# IMU_Section.net
KiCad netlist of a schematic drawn in Altium Designer
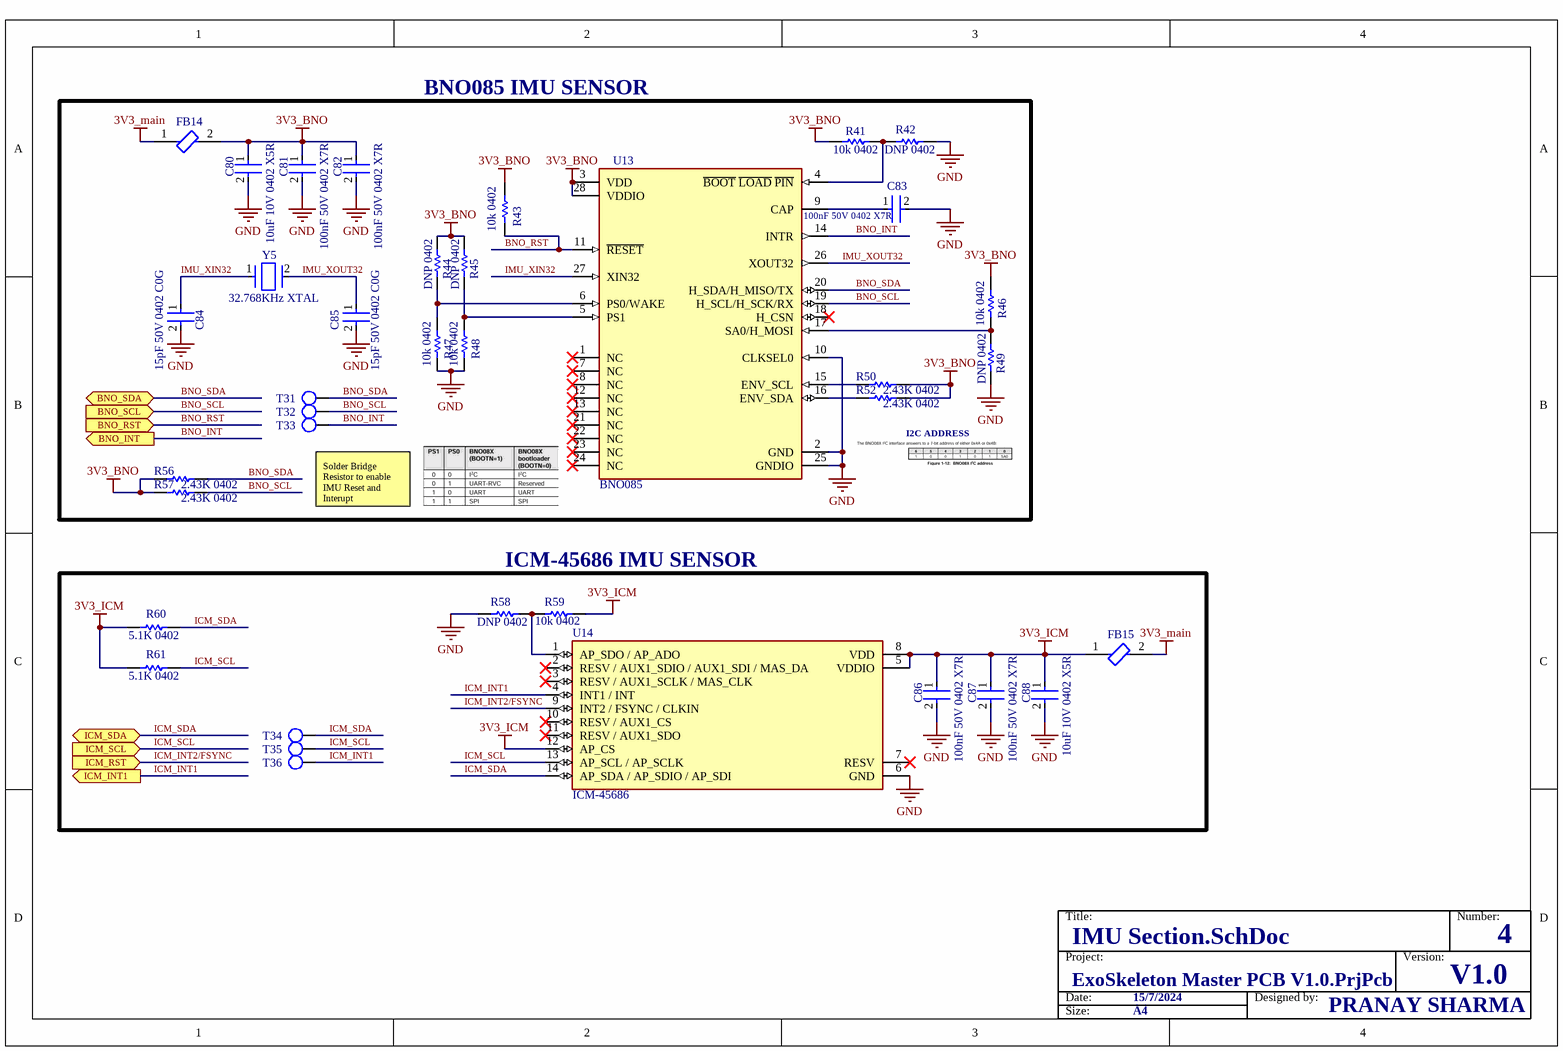
[diagram p0: IMU Section.SchDoc]

(export (version "E")
  (design (tool "Eeschema 10.0.6"))
  (components
    (comp (ref "C80")
      (value "10uF 10V 0402 X5R")
      (footprint "Res, Cap, Ind, LED, FB_Lib:0402 IPC CLASS C CAPACITOR")
      (libsource (lib "Capacitor_Lib") (part "10uF 10V 0402 X5R"))
    )
    (comp (ref "C81")
      (value "100nF 50V 0402 X7R")
      (footprint "Res, Cap, Ind, LED, FB_Lib:0402 IPC CLASS C CAPACITOR")
      (libsource (lib "Capacitor_Lib") (part "100nF 50V 0402 X7R"))
    )
    (comp (ref "C82")
      (value "100nF 50V 0402 X7R")
      (footprint "Res, Cap, Ind, LED, FB_Lib:0402 IPC CLASS C CAPACITOR")
      (libsource (lib "Capacitor_Lib") (part "100nF 50V 0402 X7R"))
    )
    (comp (ref "C83")
      (value "100nF 50V 0402 X7R")
      (footprint "Res, Cap, Ind, LED, FB_Lib:0402 IPC CLASS C CAPACITOR")
      (libsource (lib "Capacitor_Lib") (part "100nF 50V 0402 X7R"))
    )
    (comp (ref "C84")
      (value "15pF 50V 0402 C0G")
      (footprint "Res, Cap, Ind, LED, FB_Lib:0402 IPC CLASS C CAPACITOR")
      (libsource (lib "Capacitor_Lib") (part "15pF 50V 0402 C0G"))
    )
    (comp (ref "C85")
      (value "15pF 50V 0402 C0G")
      (footprint "Res, Cap, Ind, LED, FB_Lib:0402 IPC CLASS C CAPACITOR")
      (libsource (lib "Capacitor_Lib") (part "15pF 50V 0402 C0G"))
    )
    (comp (ref "C86")
      (value "100nF 50V 0402 X7R")
      (footprint "Res, Cap, Ind, LED, FB_Lib:0402 IPC CLASS C CAPACITOR")
      (libsource (lib "Capacitor_Lib") (part "100nF 50V 0402 X7R"))
    )
    (comp (ref "C87")
      (value "100nF 50V 0402 X7R")
      (footprint "Res, Cap, Ind, LED, FB_Lib:0402 IPC CLASS C CAPACITOR")
      (libsource (lib "Capacitor_Lib") (part "100nF 50V 0402 X7R"))
    )
    (comp (ref "C88")
      (value "10uF 10V 0402 X5R")
      (footprint "Res, Cap, Ind, LED, FB_Lib:0402 IPC CLASS C CAPACITOR")
      (libsource (lib "Capacitor_Lib") (part "10uF 10V 0402 X5R"))
    )
    (comp (ref "FB14")
      (value "BLM15AX102SN1D")
      (footprint "Res, Cap, Ind, LED, FB_Lib:0402 IPC CLASS C FERRITE BEAD")
      (libsource (lib "Ferrite_Bead_Lib") (part "BLM15AX102SN1D"))
    )
    (comp (ref "FB15")
      (value "BLM15AX102SN1D")
      (footprint "Res, Cap, Ind, LED, FB_Lib:0402 IPC CLASS C FERRITE BEAD")
      (libsource (lib "Ferrite_Bead_Lib") (part "BLM15AX102SN1D"))
    )
    (comp (ref "R41")
      (value "10k 0402")
      (footprint "Res, Cap, Ind, LED, FB_Lib:0402 IPC CLASS C RESISTOR")
      (libsource (lib "Resistor_Lib") (part "10k 1% 0402"))
    )
    (comp (ref "R42")
      (value "DNP 0402")
      (footprint "Res, Cap, Ind, LED, FB_Lib:0402 IPC CLASS C RESISTOR")
      (libsource (lib "Resistor_Lib") (part "0R 1% 0402"))
    )
    (comp (ref "R43")
      (value "10k 0402")
      (footprint "Res, Cap, Ind, LED, FB_Lib:0402 IPC CLASS C RESISTOR")
      (libsource (lib "Resistor_Lib") (part "10k 1% 0402"))
    )
    (comp (ref "R44")
      (value "DNP 0402")
      (footprint "Res, Cap, Ind, LED, FB_Lib:0402 IPC CLASS C RESISTOR")
      (libsource (lib "Resistor_Lib") (part "0R 1% 0402"))
    )
    (comp (ref "R45")
      (value "DNP 0402")
      (footprint "Res, Cap, Ind, LED, FB_Lib:0402 IPC CLASS C RESISTOR")
      (libsource (lib "Resistor_Lib") (part "0R 1% 0402"))
    )
    (comp (ref "R46")
      (value "10k 0402")
      (footprint "Res, Cap, Ind, LED, FB_Lib:0402 IPC CLASS C RESISTOR")
      (libsource (lib "Resistor_Lib") (part "10k 1% 0402"))
    )
    (comp (ref "R47")
      (value "10k 0402")
      (footprint "Res, Cap, Ind, LED, FB_Lib:0402 IPC CLASS C RESISTOR")
      (libsource (lib "Resistor_Lib") (part "10k 1% 0402"))
    )
    (comp (ref "R48")
      (value "10k 0402")
      (footprint "Res, Cap, Ind, LED, FB_Lib:0402 IPC CLASS C RESISTOR")
      (libsource (lib "Resistor_Lib") (part "10k 1% 0402"))
    )
    (comp (ref "R49")
      (value "DNP 0402")
      (footprint "Res, Cap, Ind, LED, FB_Lib:0402 IPC CLASS C RESISTOR")
      (libsource (lib "Resistor_Lib") (part "0R 1% 0402"))
    )
    (comp (ref "R50")
      (value "2.43K 0402")
      (footprint "Res, Cap, Ind, LED, FB_Lib:0402 IPC CLASS C RESISTOR")
      (libsource (lib "Resistor_Lib") (part "2.43K 1% 0402"))
    )
    (comp (ref "R52")
      (value "2.43K 0402")
      (footprint "Res, Cap, Ind, LED, FB_Lib:0402 IPC CLASS C RESISTOR")
      (libsource (lib "Resistor_Lib") (part "2.43K 1% 0402"))
    )
    (comp (ref "R56")
      (value "2.43K 0402")
      (footprint "Res, Cap, Ind, LED, FB_Lib:0402 IPC CLASS C RESISTOR")
      (libsource (lib "Resistor_Lib") (part "2.43K 1% 0402"))
    )
    (comp (ref "R57")
      (value "2.43K 0402")
      (footprint "Res, Cap, Ind, LED, FB_Lib:0402 IPC CLASS C RESISTOR")
      (libsource (lib "Resistor_Lib") (part "2.43K 1% 0402"))
    )
    (comp (ref "R58")
      (value "DNP 0402")
      (footprint "Res, Cap, Ind, LED, FB_Lib:0402 IPC CLASS C RESISTOR")
      (libsource (lib "Resistor_Lib") (part "0R 1% 0402"))
    )
    (comp (ref "R59")
      (value "10k 0402")
      (footprint "Res, Cap, Ind, LED, FB_Lib:0402 IPC CLASS C RESISTOR")
      (libsource (lib "Resistor_Lib") (part "10k 1% 0402"))
    )
    (comp (ref "R60")
      (value "5.1K 0402")
      (footprint "Res, Cap, Ind, LED, FB_Lib:0402 IPC CLASS C RESISTOR")
      (libsource (lib "Resistor_Lib") (part "5.1K 1% 0402"))
    )
    (comp (ref "R61")
      (value "5.1K 0402")
      (footprint "Res, Cap, Ind, LED, FB_Lib:0402 IPC CLASS C RESISTOR")
      (libsource (lib "Resistor_Lib") (part "5.1K 1% 0402"))
    )
    (comp (ref "T31")
      (value "TP")
      (footprint "Miscellaneous_Lib:Testpoint1")
      (libsource (lib "Miscellaneous_Lib") (part "Testpoint1"))
    )
    (comp (ref "T32")
      (value "TP")
      (footprint "Miscellaneous_Lib:Testpoint1")
      (libsource (lib "Miscellaneous_Lib") (part "Testpoint1"))
    )
    (comp (ref "T33")
      (value "TP")
      (footprint "Miscellaneous_Lib:Testpoint1")
      (libsource (lib "Miscellaneous_Lib") (part "Testpoint1"))
    )
    (comp (ref "T34")
      (value "TP")
      (footprint "Miscellaneous_Lib:Testpoint1")
      (libsource (lib "Miscellaneous_Lib") (part "Testpoint1"))
    )
    (comp (ref "T35")
      (value "TP")
      (footprint "Miscellaneous_Lib:Testpoint1")
      (libsource (lib "Miscellaneous_Lib") (part "Testpoint1"))
    )
    (comp (ref "T36")
      (value "TP")
      (footprint "Miscellaneous_Lib:Testpoint1")
      (libsource (lib "Miscellaneous_Lib") (part "Testpoint1"))
    )
    (comp (ref "U13")
      (value "BNO085")
      (footprint "Integrated_Circuits_Lib:LGA-28 BNO055 IPC-C")
      (libsource (lib "Integrated_Circuits_Lib") (part "BNO085"))
    )
    (comp (ref "U14")
      (value "ICM-45686")
      (footprint "Integrated_Circuits_Lib:LGA-14 ICM-45686 IPC-C")
      (libsource (lib "Integrated_Circuits_Lib") (part "ICM-45686"))
    )
    (comp (ref "Y5")
      (value "32.768KHz XTAL")
      (footprint "Crystals_and_Oscillators_Lib:SMD3215-2P IPC-C")
      (libsource (lib "Crystals_and_Oscillators_Lib") (part "H31003271C2070CY"))
    )
  )
  (nets
    (net (code "1") (name "/BNO_INT") (class "Default")
      (node (ref "T33") (pin "0") (pinfunction "0_0") (pintype "passive"))
      (node (ref "U13") (pin "14") (pinfunction "INTR_14") (pintype "output"))
    )
    (net (code "2") (name "/BNO_RST") (class "Default")
      (node (ref "R43") (pin "1") (pinfunction "1_1") (pintype "passive"))
      (node (ref "U13") (pin "11") (pinfunction "~{RESET}_11") (pintype "input"))
    )
    (net (code "3") (name "/BNO_SCL") (class "Default")
      (node (ref "R57") (pin "2") (pinfunction "2_2") (pintype "passive"))
      (node (ref "T32") (pin "0") (pinfunction "0_0") (pintype "passive"))
      (node (ref "U13") (pin "19") (pinfunction "H_SCL/H_SCK/RX_19") (pintype "bidirectional"))
    )
    (net (code "4") (name "/BNO_SDA") (class "Default")
      (node (ref "R56") (pin "2") (pinfunction "2_2") (pintype "passive"))
      (node (ref "T31") (pin "0") (pinfunction "0_0") (pintype "passive"))
      (node (ref "U13") (pin "20") (pinfunction "H_SDA/H_MISO/TX_20") (pintype "bidirectional"))
    )
    (net (code "5") (name "/ICM_INT1") (class "Default")
      (node (ref "T36") (pin "0") (pinfunction "0_0") (pintype "passive"))
      (node (ref "U14") (pin "4") (pinfunction "INT1_/_INT_4") (pintype "bidirectional"))
    )
    (net (code "6") (name "/ICM_INT2{slash}FSYNC") (class "Default")
      (node (ref "U14") (pin "9") (pinfunction "INT2_/_FSYNC_/_CLKIN_9") (pintype "bidirectional"))
    )
    (net (code "7") (name "/ICM_SCL") (class "Default")
      (node (ref "R61") (pin "2") (pinfunction "2_2") (pintype "passive"))
      (node (ref "T35") (pin "0") (pinfunction "0_0") (pintype "passive"))
      (node (ref "U14") (pin "13") (pinfunction "AP_SCL_/_AP_SCLK_13") (pintype "bidirectional"))
    )
    (net (code "8") (name "/ICM_SDA") (class "Default")
      (node (ref "R60") (pin "2") (pinfunction "2_2") (pintype "passive"))
      (node (ref "T34") (pin "0") (pinfunction "0_0") (pintype "passive"))
      (node (ref "U14") (pin "14") (pinfunction "AP_SDA_/_AP_SDIO_/_AP_SDI_14") (pintype "bidirectional"))
    )
    (net (code "9") (name "/IMU_XIN32") (class "Default")
      (node (ref "C84") (pin "1") (pinfunction "1_1") (pintype "passive"))
      (node (ref "U13") (pin "27") (pinfunction "XIN32_27") (pintype "input"))
      (node (ref "Y5") (pin "1") (pinfunction "1_1") (pintype "passive"))
    )
    (net (code "10") (name "/IMU_XOUT32") (class "Default")
      (node (ref "C85") (pin "1") (pinfunction "1_1") (pintype "passive"))
      (node (ref "U13") (pin "26") (pinfunction "XOUT32_26") (pintype "output"))
      (node (ref "Y5") (pin "2") (pinfunction "2_2") (pintype "passive"))
    )
    (net (code "11") (name "3V3_BNO") (class "Default")
      (node (ref "C80") (pin "1") (pinfunction "1_1") (pintype "passive"))
      (node (ref "C81") (pin "1") (pinfunction "1_1") (pintype "passive"))
      (node (ref "C82") (pin "1") (pinfunction "1_1") (pintype "passive"))
      (node (ref "FB14") (pin "2") (pinfunction "2_2") (pintype "passive"))
      (node (ref "R41") (pin "1") (pinfunction "1_1") (pintype "passive"))
      (node (ref "R43") (pin "2") (pinfunction "2_2") (pintype "passive"))
      (node (ref "R44") (pin "2") (pinfunction "2_2") (pintype "passive"))
      (node (ref "R45") (pin "2") (pinfunction "2_2") (pintype "passive"))
      (node (ref "R46") (pin "2") (pinfunction "2_2") (pintype "passive"))
      (node (ref "R50") (pin "2") (pinfunction "2_2") (pintype "passive"))
      (node (ref "R52") (pin "2") (pinfunction "2_2") (pintype "passive"))
      (node (ref "R56") (pin "1") (pinfunction "1_1") (pintype "passive"))
      (node (ref "R57") (pin "1") (pinfunction "1_1") (pintype "passive"))
      (node (ref "U13") (pin "28") (pinfunction "VDDIO_28") (pintype "power_in"))
      (node (ref "U13") (pin "3") (pinfunction "VDD_3") (pintype "power_in"))
    )
    (net (code "12") (name "3V3_ICM") (class "Default")
      (node (ref "C86") (pin "1") (pinfunction "1_1") (pintype "passive"))
      (node (ref "C87") (pin "1") (pinfunction "1_1") (pintype "passive"))
      (node (ref "C88") (pin "1") (pinfunction "1_1") (pintype "passive"))
      (node (ref "FB15") (pin "1") (pinfunction "1_1") (pintype "passive"))
      (node (ref "R59") (pin "1") (pinfunction "1_1") (pintype "passive"))
      (node (ref "R60") (pin "1") (pinfunction "1_1") (pintype "passive"))
      (node (ref "R61") (pin "1") (pinfunction "1_1") (pintype "passive"))
      (node (ref "U14") (pin "12") (pinfunction "AP_CS_12") (pintype "bidirectional"))
      (node (ref "U14") (pin "5") (pinfunction "VDDIO_5") (pintype "power_in"))
      (node (ref "U14") (pin "8") (pinfunction "VDD_8") (pintype "power_in"))
    )
    (net (code "13") (name "3V3_main") (class "Default")
      (node (ref "FB14") (pin "1") (pinfunction "1_1") (pintype "passive"))
      (node (ref "FB15") (pin "2") (pinfunction "2_2") (pintype "passive"))
    )
    (net (code "14") (name "GND") (class "Default")
      (node (ref "C80") (pin "2") (pinfunction "2_2") (pintype "passive"))
      (node (ref "C81") (pin "2") (pinfunction "2_2") (pintype "passive"))
      (node (ref "C82") (pin "2") (pinfunction "2_2") (pintype "passive"))
      (node (ref "C83") (pin "2") (pinfunction "2_2") (pintype "passive"))
      (node (ref "C84") (pin "2") (pinfunction "2_2") (pintype "passive"))
      (node (ref "C85") (pin "2") (pinfunction "2_2") (pintype "passive"))
      (node (ref "C86") (pin "2") (pinfunction "2_2") (pintype "passive"))
      (node (ref "C87") (pin "2") (pinfunction "2_2") (pintype "passive"))
      (node (ref "C88") (pin "2") (pinfunction "2_2") (pintype "passive"))
      (node (ref "R42") (pin "1") (pinfunction "1_1") (pintype "passive"))
      (node (ref "R47") (pin "1") (pinfunction "1_1") (pintype "passive"))
      (node (ref "R48") (pin "1") (pinfunction "1_1") (pintype "passive"))
      (node (ref "R49") (pin "1") (pinfunction "1_1") (pintype "passive"))
      (node (ref "R58") (pin "2") (pinfunction "2_2") (pintype "passive"))
      (node (ref "U13") (pin "10") (pinfunction "CLKSEL0_10") (pintype "input"))
      (node (ref "U13") (pin "2") (pinfunction "GND_2") (pintype "power_in"))
      (node (ref "U13") (pin "25") (pinfunction "GNDIO_25") (pintype "power_in"))
      (node (ref "U14") (pin "6") (pinfunction "GND_6") (pintype "power_in"))
    )
    (net (code "15") (name "Net-(U13-CAP)") (class "Default")
      (node (ref "C83") (pin "1") (pinfunction "1_1") (pintype "passive"))
      (node (ref "U13") (pin "9") (pinfunction "CAP_9") (pintype "power_in"))
    )
    (net (code "16") (name "Net-(U13-ENV_SCL)") (class "Default")
      (node (ref "R50") (pin "1") (pinfunction "1_1") (pintype "passive"))
      (node (ref "U13") (pin "15") (pinfunction "ENV_SCL_15") (pintype "input"))
    )
    (net (code "17") (name "Net-(U13-ENV_SDA)") (class "Default")
      (node (ref "R52") (pin "1") (pinfunction "1_1") (pintype "passive"))
      (node (ref "U13") (pin "16") (pinfunction "ENV_SDA_16") (pintype "bidirectional"))
    )
    (net (code "18") (name "Net-(U13-PS0{slash}WAKE)") (class "Default")
      (node (ref "R44") (pin "1") (pinfunction "1_1") (pintype "passive"))
      (node (ref "R47") (pin "2") (pinfunction "2_2") (pintype "passive"))
      (node (ref "U13") (pin "6") (pinfunction "PS0/WAKE_6") (pintype "input"))
    )
    (net (code "19") (name "Net-(U13-PS1)") (class "Default")
      (node (ref "R45") (pin "1") (pinfunction "1_1") (pintype "passive"))
      (node (ref "R48") (pin "2") (pinfunction "2_2") (pintype "passive"))
      (node (ref "U13") (pin "5") (pinfunction "PS1_5") (pintype "input"))
    )
    (net (code "20") (name "Net-(U13-SA0{slash}H_MOSI)") (class "Default")
      (node (ref "R46") (pin "1") (pinfunction "1_1") (pintype "passive"))
      (node (ref "R49") (pin "2") (pinfunction "2_2") (pintype "passive"))
      (node (ref "U13") (pin "17") (pinfunction "SA0/H_MOSI_17") (pintype "input"))
    )
    (net (code "21") (name "Net-(U13-~{BOOT}_~{LOAD}_~{PIN})") (class "Default")
      (node (ref "R41") (pin "2") (pinfunction "2_2") (pintype "passive"))
      (node (ref "R42") (pin "2") (pinfunction "2_2") (pintype "passive"))
      (node (ref "U13") (pin "4") (pinfunction "~{BOOT}_~{LOAD}_~{PIN}_4") (pintype "input"))
    )
    (net (code "22") (name "Net-(U14-AP_SDO_{slash}_AP_ADO)") (class "Default")
      (node (ref "R58") (pin "1") (pinfunction "1_1") (pintype "passive"))
      (node (ref "R59") (pin "2") (pinfunction "2_2") (pintype "passive"))
      (node (ref "U14") (pin "1") (pinfunction "AP_SDO_/_AP_ADO_1") (pintype "bidirectional"))
    )
    (net (code "23") (name "unconnected-(U13-H_CSN-Pad18)") (class "Default")
      (node (ref "U13") (pin "18") (pinfunction "H_CSN_18") (pintype "bidirectional+no_connect"))
    )
    (net (code "24") (name "unconnected-(U13-NC-Pad1)") (class "Default")
      (node (ref "U13") (pin "1") (pinfunction "NC_1") (pintype "passive+no_connect"))
    )
    (net (code "25") (name "unconnected-(U13-NC-Pad7)") (class "Default")
      (node (ref "U13") (pin "7") (pinfunction "NC_7") (pintype "passive+no_connect"))
    )
    (net (code "26") (name "unconnected-(U13-NC-Pad8)") (class "Default")
      (node (ref "U13") (pin "8") (pinfunction "NC_8") (pintype "passive+no_connect"))
    )
    (net (code "27") (name "unconnected-(U13-NC-Pad12)") (class "Default")
      (node (ref "U13") (pin "12") (pinfunction "NC_12") (pintype "passive+no_connect"))
    )
    (net (code "28") (name "unconnected-(U13-NC-Pad13)") (class "Default")
      (node (ref "U13") (pin "13") (pinfunction "NC_13") (pintype "passive+no_connect"))
    )
    (net (code "29") (name "unconnected-(U13-NC-Pad21)") (class "Default")
      (node (ref "U13") (pin "21") (pinfunction "NC_21") (pintype "passive+no_connect"))
    )
    (net (code "30") (name "unconnected-(U13-NC-Pad22)") (class "Default")
      (node (ref "U13") (pin "22") (pinfunction "NC_22") (pintype "passive+no_connect"))
    )
    (net (code "31") (name "unconnected-(U13-NC-Pad23)") (class "Default")
      (node (ref "U13") (pin "23") (pinfunction "NC_23") (pintype "passive+no_connect"))
    )
    (net (code "32") (name "unconnected-(U13-NC-Pad24)") (class "Default")
      (node (ref "U13") (pin "24") (pinfunction "NC_24") (pintype "passive+no_connect"))
    )
    (net (code "33") (name "unconnected-(U14-RESV-Pad7)") (class "Default")
      (node (ref "U14") (pin "7") (pinfunction "RESV_7") (pintype "passive+no_connect"))
    )
    (net (code "34") (name "unconnected-(U14-RESV_{slash}_AUX1_CS-Pad10)") (class "Default")
      (node (ref "U14") (pin "10") (pinfunction "RESV_/_AUX1_CS_10") (pintype "bidirectional+no_connect"))
    )
    (net (code "35") (name "unconnected-(U14-RESV_{slash}_AUX1_SCLK_{slash}_MAS_CLK-Pad3)") (class "Default")
      (node (ref "U14") (pin "3") (pinfunction "RESV_/_AUX1_SCLK_/_MAS_CLK_3") (pintype "bidirectional+no_connect"))
    )
    (net (code "36") (name "unconnected-(U14-RESV_{slash}_AUX1_SDIO_{slash}_AUX1_SDI_{slash}_MAS_DA-Pad2)") (class "Default")
      (node (ref "U14") (pin "2") (pinfunction "RESV_/_AUX1_SDIO_/_AUX1_SDI_/_MAS_DA_2") (pintype "bidirectional+no_connect"))
    )
    (net (code "37") (name "unconnected-(U14-RESV_{slash}_AUX1_SDO-Pad11)") (class "Default")
      (node (ref "U14") (pin "11") (pinfunction "RESV_/_AUX1_SDO_11") (pintype "bidirectional+no_connect"))
    )
  )
)
